# magicmouth-v0_1.net
KiCad netlist of a schematic drawn in EAGLE
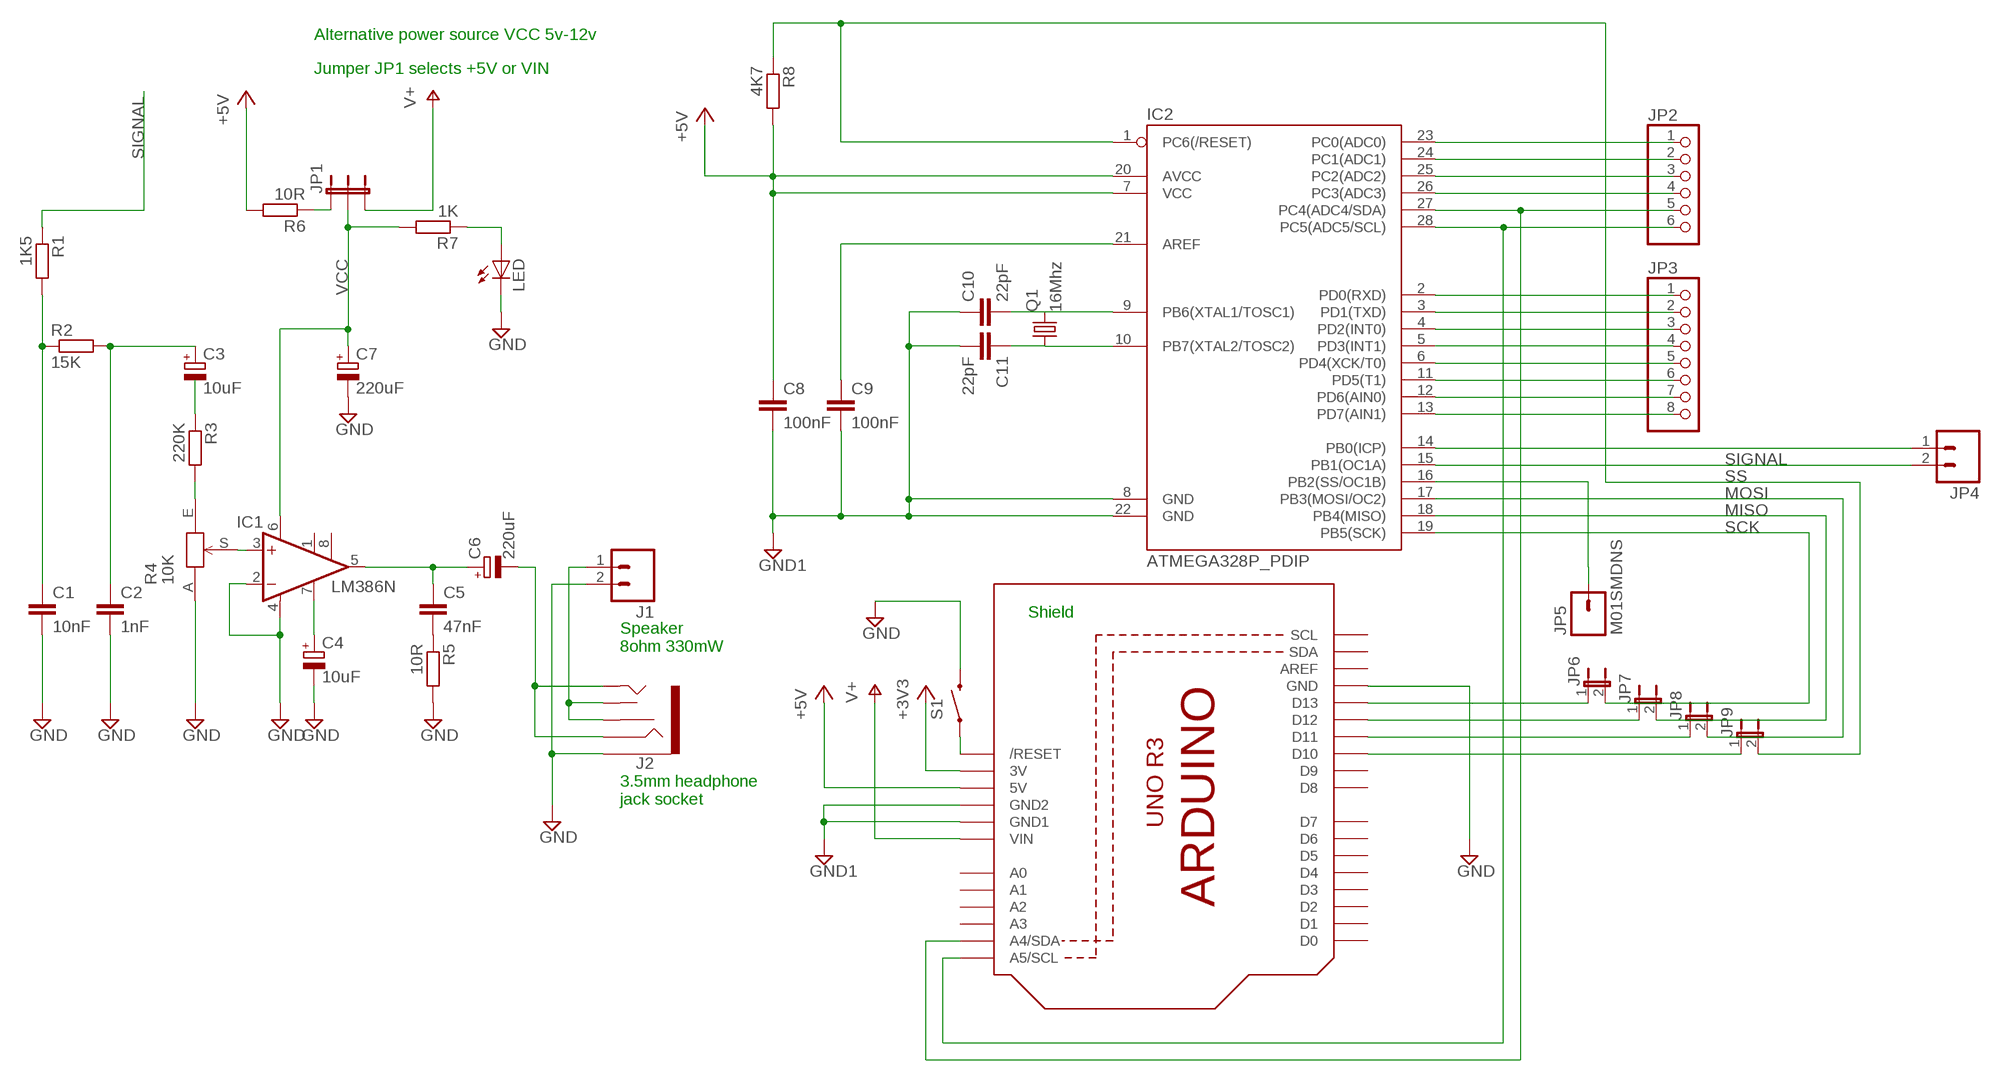
[diagram p0: schematic, sheet 1]

(export (version "E")
  (design (tool "Eeschema 10.0.6"))
  (components
    (comp (ref "C1")
      (value "10nF")
      (footprint "eagle-import:C050-025X075")
      (libsource (lib "eagle-import") (part "resistor_C-EU050-025X075"))
    )
    (comp (ref "C2")
      (value "1nF")
      (footprint "eagle-import:C050-025X075")
      (libsource (lib "eagle-import") (part "resistor_C-EU050-025X075"))
    )
    (comp (ref "C3")
      (value "10uF")
      (footprint "eagle-import:E2,5-7")
      (libsource (lib "eagle-import") (part "CPOL-EUE2.5-7"))
    )
    (comp (ref "C4")
      (value "10uF")
      (footprint "eagle-import:E2,5-7")
      (libsource (lib "eagle-import") (part "CPOL-EUE2.5-7"))
    )
    (comp (ref "C5")
      (value "47nF")
      (footprint "eagle-import:C050-025X075")
      (libsource (lib "eagle-import") (part "resistor_C-EU050-025X075"))
    )
    (comp (ref "C6")
      (value "220uF")
      (footprint "eagle-import:TT5D7L")
      (libsource (lib "eagle-import") (part "CPOL-EUTT5D7L"))
    )
    (comp (ref "C7")
      (value "220uF")
      (footprint "eagle-import:TT5D7L")
      (libsource (lib "eagle-import") (part "CPOL-EUTT5D7L"))
    )
    (comp (ref "C8")
      (value "100nF")
      (footprint "eagle-import:C025-025X050")
      (fields (field (name "CAPACITANCE") "10 nF"))
      (libsource (lib "eagle-import") (part "C-EU025-025X050"))
    )
    (comp (ref "C9")
      (value "100nF")
      (footprint "eagle-import:C025-025X050")
      (fields (field (name "CAPACITANCE") "100 nF"))
      (libsource (lib "eagle-import") (part "C-EU025-025X050"))
    )
    (comp (ref "C10")
      (value "22pF")
      (footprint "eagle-import:C025-025X050")
      (fields (field (name "CAPACITANCE") "22 pf"))
      (libsource (lib "eagle-import") (part "C-EU025-025X050"))
    )
    (comp (ref "C11")
      (value "22pF")
      (footprint "eagle-import:C025-025X050")
      (fields (field (name "CAPACITANCE") "22 pf"))
      (libsource (lib "eagle-import") (part "C-EU025-025X050"))
    )
    (comp (ref "IC1")
      (value "LM386N")
      (footprint "eagle-import:DIL08")
      (libsource (lib "eagle-import") (part "LM386?-N1"))
    )
    (comp (ref "IC2")
      (value "ATMEGA328P_PDIP")
      (footprint "eagle-import:DIL28-3")
      (libsource (lib "eagle-import") (part "ATMEGA328P_PDIP"))
    )
    (comp (ref "J1")
      (value "M023.5MM")
      (footprint "eagle-import:SCREWTERMINAL-3.5MM-2")
      (libsource (lib "eagle-import") (part "M023.5MM"))
    )
    (comp (ref "J2")
      (value "AUDIO-JACK2PTH")
      (footprint "eagle-import:AUDIO-JACK")
      (libsource (lib "eagle-import") (part "AUDIO-JACK2PTH"))
    )
    (comp (ref "JP1")
      (value "JUMPER-3PTH")
      (footprint "eagle-import:1X03")
      (libsource (lib "eagle-import") (part "JUMPER-3PTH"))
    )
    (comp (ref "JP2")
      (value "PINHD-1X6CB")
      (footprint "eagle-import:1X06-CLEANBIG")
      (libsource (lib "eagle-import") (part "PINHD-1X6CB"))
    )
    (comp (ref "JP3")
      (value "PINHD-1X8CLEANBIG")
      (footprint "eagle-import:1X08-CLEANBIG")
      (libsource (lib "eagle-import") (part "PINHD-1X8CLEANBIG"))
    )
    (comp (ref "JP4")
      (value "M021X02_NO_SILK")
      (footprint "eagle-import:1X02_NO_SILK")
      (libsource (lib "eagle-import") (part "M021X02_NO_SILK"))
    )
    (comp (ref "JP5")
      (value "M01SMDNS")
      (footprint "eagle-import:1X01NS")
      (libsource (lib "eagle-import") (part "M01SMDNS"))
    )
    (comp (ref "JP6")
      (value "JUMPER-2PTH")
      (footprint "eagle-import:1X02")
      (libsource (lib "eagle-import") (part "JUMPER-2PTH"))
    )
    (comp (ref "JP7")
      (value "JUMPER-2PTH")
      (footprint "eagle-import:1X02")
      (libsource (lib "eagle-import") (part "JUMPER-2PTH"))
    )
    (comp (ref "JP8")
      (value "JUMPER-2PTH")
      (footprint "eagle-import:1X02")
      (libsource (lib "eagle-import") (part "JUMPER-2PTH"))
    )
    (comp (ref "JP9")
      (value "JUMPER-2PTH")
      (footprint "eagle-import:1X02")
      (libsource (lib "eagle-import") (part "JUMPER-2PTH"))
    )
    (comp (ref "LED")
      (value "LED3MM")
      (footprint "eagle-import:LED3MM")
      (libsource (lib "eagle-import") (part "LED3MM"))
    )
    (comp (ref "Q1")
      (value "16Mhz")
      (footprint "eagle-import:HC49_S")
      (libsource (lib "eagle-import") (part "CRYSTALHC49S"))
    )
    (comp (ref "R1")
      (value "1K5")
      (footprint "eagle-import:0207_7")
      (libsource (lib "eagle-import") (part "R-EU_0207/7"))
    )
    (comp (ref "R2")
      (value "15K")
      (footprint "eagle-import:0207_7")
      (libsource (lib "eagle-import") (part "R-EU_0207/7"))
    )
    (comp (ref "R3")
      (value "220K")
      (footprint "eagle-import:0207_7")
      (libsource (lib "eagle-import") (part "R-EU_0207/7"))
    )
    (comp (ref "R4")
      (value "10K")
      (footprint "eagle-import:3352T")
      (libsource (lib "eagle-import") (part "TPOT3352"))
    )
    (comp (ref "R5")
      (value "10R")
      (footprint "eagle-import:0207_7")
      (libsource (lib "eagle-import") (part "resistor_R-EU_0207/7"))
    )
    (comp (ref "R6")
      (value "10R")
      (footprint "eagle-import:0207_7")
      (libsource (lib "eagle-import") (part "R-EU_0207/7"))
    )
    (comp (ref "R7")
      (value "1K")
      (footprint "eagle-import:0207_7")
      (libsource (lib "eagle-import") (part "R-EU_0207/7"))
    )
    (comp (ref "R8")
      (value "4K7")
      (footprint "eagle-import:0207_7")
      (fields (field (name "RESISTANCE") "4K7"))
      (libsource (lib "eagle-import") (part "R-EU_0207/7"))
    )
    (comp (ref "S1")
      (value "SWITCH-MOMENTARY-2PTH")
      (footprint "eagle-import:TACTILE-PTH")
      (libsource (lib "eagle-import") (part "SWITCH-MOMENTARY-2PTH"))
    )
    (comp (ref "U1")
      (value "ARDUINOR3-NOIOREF-NOTEXT")
      (footprint "eagle-import:ARDUINOR3-NOTEXT-NOIOREF")
      (libsource (lib "eagle-import") (part "ARDUINOR3-NOIOREF-NOTEXT"))
    )
  )
  (nets
    (net (code "1") (name "+3V3") (class "Default")
      (node (ref "U1") (pin "3V") (pinfunction "3V_3V") (pintype "power_in"))
    )
    (net (code "2") (name "+5V") (class "Default")
      (node (ref "C8") (pin "1") (pinfunction "1_1") (pintype "passive"))
      (node (ref "IC2") (pin "20") (pinfunction "AVCC_20") (pintype "bidirectional"))
      (node (ref "IC2") (pin "7") (pinfunction "VCC_7") (pintype "bidirectional"))
      (node (ref "R6") (pin "2") (pinfunction "2_2") (pintype "passive"))
      (node (ref "R8") (pin "2") (pinfunction "2_2") (pintype "passive"))
      (node (ref "U1") (pin "5V") (pinfunction "5V_5V") (pintype "power_in"))
    )
    (net (code "3") (name "/MISO") (class "Default")
      (node (ref "IC2") (pin "18") (pinfunction "PB4(MISO)_18") (pintype "bidirectional"))
      (node (ref "JP7") (pin "2") (pinfunction "2_2") (pintype "passive"))
    )
    (net (code "4") (name "/MOSI") (class "Default")
      (node (ref "IC2") (pin "17") (pinfunction "PB3(MOSI/OC2)_17") (pintype "bidirectional"))
      (node (ref "JP8") (pin "2") (pinfunction "2_2") (pintype "passive"))
    )
    (net (code "5") (name "/SCK") (class "Default")
      (node (ref "IC2") (pin "19") (pinfunction "PB5(SCK)_19") (pintype "bidirectional"))
      (node (ref "JP6") (pin "2") (pinfunction "2_2") (pintype "passive"))
    )
    (net (code "6") (name "/SIGNAL") (class "Default")
      (node (ref "IC2") (pin "15") (pinfunction "PB1(OC1A)_15") (pintype "bidirectional"))
      (node (ref "JP4") (pin "2") (pinfunction "2_2") (pintype "passive"))
      (node (ref "R1") (pin "1") (pinfunction "1_1") (pintype "passive"))
    )
    (net (code "7") (name "/SS") (class "Default")
      (node (ref "IC2") (pin "1") (pinfunction "PC6(/RESET)_1") (pintype "bidirectional"))
      (node (ref "JP9") (pin "2") (pinfunction "2_2") (pintype "passive"))
      (node (ref "R8") (pin "1") (pinfunction "1_1") (pintype "passive"))
    )
    (net (code "8") (name "/VCC") (class "Default")
      (node (ref "C7") (pin "+") (pinfunction "+_+") (pintype "passive"))
      (node (ref "IC1") (pin "6") (pinfunction "VS_6") (pintype "power_in"))
      (node (ref "JP1") (pin "2") (pinfunction "2_2") (pintype "passive"))
      (node (ref "R7") (pin "2") (pinfunction "2_2") (pintype "passive"))
    )
    (net (code "9") (name "GND") (class "Default")
      (node (ref "C1") (pin "2") (pinfunction "2_2") (pintype "passive"))
      (node (ref "C2") (pin "2") (pinfunction "2_2") (pintype "passive"))
      (node (ref "C4") (pin "-") (pinfunction "-_-") (pintype "passive"))
      (node (ref "C7") (pin "-") (pinfunction "-_-") (pintype "passive"))
      (node (ref "IC1") (pin "2") (pinfunction "-IN_2") (pintype "input"))
      (node (ref "IC1") (pin "4") (pinfunction "GND_4") (pintype "power_in"))
      (node (ref "J1") (pin "2") (pinfunction "2_2") (pintype "passive"))
      (node (ref "J2") (pin "SLEEVE") (pinfunction "SLEEVE_SLEEVE") (pintype "bidirectional"))
      (node (ref "LED") (pin "K") (pinfunction "C_K") (pintype "passive"))
      (node (ref "R4") (pin "A") (pinfunction "A_A") (pintype "passive"))
      (node (ref "R5") (pin "2") (pinfunction "2_2") (pintype "passive"))
      (node (ref "S1") (pin "3") (pinfunction "2_3") (pintype "passive"))
      (node (ref "U1") (pin "GND") (pinfunction "GND_GND") (pintype "power_in"))
    )
    (net (code "10") (name "GND1") (class "Default")
      (node (ref "C10") (pin "1") (pinfunction "1_1") (pintype "passive"))
      (node (ref "C11") (pin "2") (pinfunction "2_2") (pintype "passive"))
      (node (ref "C8") (pin "2") (pinfunction "2_2") (pintype "passive"))
      (node (ref "C9") (pin "2") (pinfunction "2_2") (pintype "passive"))
      (node (ref "IC2") (pin "22") (pinfunction "GND_22") (pintype "bidirectional"))
      (node (ref "IC2") (pin "8") (pinfunction "GND_8") (pintype "bidirectional"))
      (node (ref "U1") (pin "GND1") (pinfunction "GND1_GND1") (pintype "power_in"))
      (node (ref "U1") (pin "GND2") (pinfunction "GND2_GND2") (pintype "power_in"))
    )
    (net (code "11") (name "Net-(C1-Pad1)") (class "Default")
      (node (ref "C1") (pin "1") (pinfunction "1_1") (pintype "passive"))
      (node (ref "R1") (pin "2") (pinfunction "2_2") (pintype "passive"))
      (node (ref "R2") (pin "1") (pinfunction "1_1") (pintype "passive"))
    )
    (net (code "12") (name "Net-(C2-Pad1)") (class "Default")
      (node (ref "C2") (pin "1") (pinfunction "1_1") (pintype "passive"))
      (node (ref "C3") (pin "+") (pinfunction "+_+") (pintype "passive"))
      (node (ref "R2") (pin "2") (pinfunction "2_2") (pintype "passive"))
    )
    (net (code "13") (name "Net-(C3-Pad-)") (class "Default")
      (node (ref "C3") (pin "-") (pinfunction "-_-") (pintype "passive"))
      (node (ref "R3") (pin "1") (pinfunction "1_1") (pintype "passive"))
    )
    (net (code "14") (name "Net-(C5-Pad2)") (class "Default")
      (node (ref "C5") (pin "2") (pinfunction "2_2") (pintype "passive"))
      (node (ref "R5") (pin "1") (pinfunction "1_1") (pintype "passive"))
    )
    (net (code "15") (name "Net-(C6-Pad-)") (class "Default")
      (node (ref "C6") (pin "-") (pinfunction "-_-") (pintype "passive"))
      (node (ref "J2") (pin "RING") (pinfunction "RING_RING") (pintype "bidirectional"))
      (node (ref "J2") (pin "TIP") (pinfunction "TIP_TIP") (pintype "bidirectional"))
    )
    (net (code "16") (name "Net-(IC1-+IN)") (class "Default")
      (node (ref "IC1") (pin "3") (pinfunction "+IN_3") (pintype "input"))
      (node (ref "R4") (pin "S") (pinfunction "S_S") (pintype "passive"))
    )
    (net (code "17") (name "Net-(IC1-BYPASS)") (class "Default")
      (node (ref "C4") (pin "+") (pinfunction "+_+") (pintype "passive"))
      (node (ref "IC1") (pin "7") (pinfunction "BYPASS_7") (pintype "passive"))
    )
    (net (code "18") (name "Net-(IC1-OUT)") (class "Default")
      (node (ref "C5") (pin "1") (pinfunction "1_1") (pintype "passive"))
      (node (ref "C6") (pin "+") (pinfunction "+_+") (pintype "passive"))
      (node (ref "IC1") (pin "5") (pinfunction "OUT_5") (pintype "output"))
    )
    (net (code "19") (name "Net-(IC2-AREF)") (class "Default")
      (node (ref "C9") (pin "1") (pinfunction "1_1") (pintype "passive"))
      (node (ref "IC2") (pin "21") (pinfunction "AREF_21") (pintype "bidirectional"))
    )
    (net (code "20") (name "Net-(IC2-PB0(ICP))") (class "Default")
      (node (ref "IC2") (pin "14") (pinfunction "PB0(ICP)_14") (pintype "bidirectional"))
      (node (ref "JP4") (pin "1") (pinfunction "1_1") (pintype "passive"))
    )
    (net (code "21") (name "Net-(IC2-PB2(SS{slash}OC1B))") (class "Default")
      (node (ref "IC2") (pin "16") (pinfunction "PB2(SS/OC1B)_16") (pintype "bidirectional"))
      (node (ref "JP5") (pin "1") (pinfunction "1_1") (pintype "passive"))
    )
    (net (code "22") (name "Net-(IC2-PB6(XTAL1{slash}TOSC1))") (class "Default")
      (node (ref "C10") (pin "2") (pinfunction "2_2") (pintype "passive"))
      (node (ref "IC2") (pin "9") (pinfunction "PB6(XTAL1/TOSC1)_9") (pintype "bidirectional"))
      (node (ref "Q1") (pin "2") (pinfunction "2_2") (pintype "passive"))
    )
    (net (code "23") (name "Net-(IC2-PB7(XTAL2{slash}TOSC2))") (class "Default")
      (node (ref "C11") (pin "1") (pinfunction "1_1") (pintype "passive"))
      (node (ref "IC2") (pin "10") (pinfunction "PB7(XTAL2/TOSC2)_10") (pintype "bidirectional"))
      (node (ref "Q1") (pin "1") (pinfunction "1_1") (pintype "passive"))
    )
    (net (code "24") (name "Net-(IC2-PC0(ADC0))") (class "Default")
      (node (ref "IC2") (pin "23") (pinfunction "PC0(ADC0)_23") (pintype "bidirectional"))
      (node (ref "JP2") (pin "1") (pinfunction "1_1") (pintype "passive"))
    )
    (net (code "25") (name "Net-(IC2-PC1(ADC1))") (class "Default")
      (node (ref "IC2") (pin "24") (pinfunction "PC1(ADC1)_24") (pintype "bidirectional"))
      (node (ref "JP2") (pin "2") (pinfunction "2_2") (pintype "passive"))
    )
    (net (code "26") (name "Net-(IC2-PC2(ADC2))") (class "Default")
      (node (ref "IC2") (pin "25") (pinfunction "PC2(ADC2)_25") (pintype "bidirectional"))
      (node (ref "JP2") (pin "3") (pinfunction "3_3") (pintype "passive"))
    )
    (net (code "27") (name "Net-(IC2-PC3(ADC3))") (class "Default")
      (node (ref "IC2") (pin "26") (pinfunction "PC3(ADC3)_26") (pintype "bidirectional"))
      (node (ref "JP2") (pin "4") (pinfunction "4_4") (pintype "passive"))
    )
    (net (code "28") (name "Net-(IC2-PC4(ADC4{slash}SDA))") (class "Default")
      (node (ref "IC2") (pin "27") (pinfunction "PC4(ADC4/SDA)_27") (pintype "bidirectional"))
      (node (ref "JP2") (pin "5") (pinfunction "5_5") (pintype "passive"))
      (node (ref "U1") (pin "A4") (pinfunction "A4/SDA_A4") (pintype "bidirectional"))
    )
    (net (code "29") (name "Net-(IC2-PC5(ADC5{slash}SCL))") (class "Default")
      (node (ref "IC2") (pin "28") (pinfunction "PC5(ADC5/SCL)_28") (pintype "bidirectional"))
      (node (ref "JP2") (pin "6") (pinfunction "6_6") (pintype "passive"))
      (node (ref "U1") (pin "A5") (pinfunction "A5/SCL_A5") (pintype "bidirectional"))
    )
    (net (code "30") (name "Net-(IC2-PD0(RXD))") (class "Default")
      (node (ref "IC2") (pin "2") (pinfunction "PD0(RXD)_2") (pintype "bidirectional"))
      (node (ref "JP3") (pin "1") (pinfunction "1_1") (pintype "passive"))
    )
    (net (code "31") (name "Net-(IC2-PD1(TXD))") (class "Default")
      (node (ref "IC2") (pin "3") (pinfunction "PD1(TXD)_3") (pintype "bidirectional"))
      (node (ref "JP3") (pin "2") (pinfunction "2_2") (pintype "passive"))
    )
    (net (code "32") (name "Net-(IC2-PD2(INT0))") (class "Default")
      (node (ref "IC2") (pin "4") (pinfunction "PD2(INT0)_4") (pintype "bidirectional"))
      (node (ref "JP3") (pin "3") (pinfunction "3_3") (pintype "passive"))
    )
    (net (code "33") (name "Net-(IC2-PD3(INT1))") (class "Default")
      (node (ref "IC2") (pin "5") (pinfunction "PD3(INT1)_5") (pintype "bidirectional"))
      (node (ref "JP3") (pin "4") (pinfunction "4_4") (pintype "passive"))
    )
    (net (code "34") (name "Net-(IC2-PD4(XCK{slash}T0))") (class "Default")
      (node (ref "IC2") (pin "6") (pinfunction "PD4(XCK/T0)_6") (pintype "bidirectional"))
      (node (ref "JP3") (pin "5") (pinfunction "5_5") (pintype "passive"))
    )
    (net (code "35") (name "Net-(IC2-PD5(T1))") (class "Default")
      (node (ref "IC2") (pin "11") (pinfunction "PD5(T1)_11") (pintype "bidirectional"))
      (node (ref "JP3") (pin "6") (pinfunction "6_6") (pintype "passive"))
    )
    (net (code "36") (name "Net-(IC2-PD6(AIN0))") (class "Default")
      (node (ref "IC2") (pin "12") (pinfunction "PD6(AIN0)_12") (pintype "bidirectional"))
      (node (ref "JP3") (pin "7") (pinfunction "7_7") (pintype "passive"))
    )
    (net (code "37") (name "Net-(IC2-PD7(AIN1))") (class "Default")
      (node (ref "IC2") (pin "13") (pinfunction "PD7(AIN1)_13") (pintype "bidirectional"))
      (node (ref "JP3") (pin "8") (pinfunction "8_8") (pintype "passive"))
    )
    (net (code "38") (name "Net-(J1-Pad1)") (class "Default")
      (node (ref "J1") (pin "1") (pinfunction "1_1") (pintype "passive"))
      (node (ref "J2") (pin "RSH") (pinfunction "RSH_RSH") (pintype "bidirectional"))
      (node (ref "J2") (pin "TSH") (pinfunction "TSH_TSH") (pintype "bidirectional"))
    )
    (net (code "39") (name "Net-(JP1-Pad1)") (class "Default")
      (node (ref "JP1") (pin "1") (pinfunction "1_1") (pintype "passive"))
      (node (ref "R6") (pin "1") (pinfunction "1_1") (pintype "passive"))
    )
    (net (code "40") (name "Net-(JP6-Pad1)") (class "Default")
      (node (ref "JP6") (pin "1") (pinfunction "1_1") (pintype "passive"))
      (node (ref "U1") (pin "D13") (pinfunction "D13_D13") (pintype "bidirectional"))
    )
    (net (code "41") (name "Net-(JP7-Pad1)") (class "Default")
      (node (ref "JP7") (pin "1") (pinfunction "1_1") (pintype "passive"))
      (node (ref "U1") (pin "D12") (pinfunction "D12_D12") (pintype "bidirectional"))
    )
    (net (code "42") (name "Net-(JP8-Pad1)") (class "Default")
      (node (ref "JP8") (pin "1") (pinfunction "1_1") (pintype "passive"))
      (node (ref "U1") (pin "D11") (pinfunction "D11_D11") (pintype "bidirectional"))
    )
    (net (code "43") (name "Net-(JP9-Pad1)") (class "Default")
      (node (ref "JP9") (pin "1") (pinfunction "1_1") (pintype "passive"))
      (node (ref "U1") (pin "D10") (pinfunction "D10_D10") (pintype "bidirectional"))
    )
    (net (code "44") (name "Net-(LED-PadA)") (class "Default")
      (node (ref "LED") (pin "A") (pinfunction "A_A") (pintype "passive"))
      (node (ref "R7") (pin "1") (pinfunction "1_1") (pintype "passive"))
    )
    (net (code "45") (name "Net-(R3-Pad2)") (class "Default")
      (node (ref "R3") (pin "2") (pinfunction "2_2") (pintype "passive"))
      (node (ref "R4") (pin "E") (pinfunction "E_E") (pintype "passive"))
    )
    (net (code "46") (name "Net-(U1-{slash}RESET)") (class "Default")
      (node (ref "S1") (pin "1") (pinfunction "1_1") (pintype "passive"))
      (node (ref "U1") (pin "RESET") (pinfunction "/RESET_RESET") (pintype "bidirectional"))
    )
    (net (code "47") (name "V+") (class "Default")
      (node (ref "JP1") (pin "3") (pinfunction "3_3") (pintype "passive"))
      (node (ref "U1") (pin "VIN") (pinfunction "VIN_VIN") (pintype "power_in"))
    )
    (net (code "48") (name "unconnected-(IC1-GAIN-Pad1)") (class "Default")
      (node (ref "IC1") (pin "1") (pinfunction "GAIN_1") (pintype "passive"))
    )
    (net (code "49") (name "unconnected-(IC1-GAIN-Pad8)") (class "Default")
      (node (ref "IC1") (pin "8") (pinfunction "GAIN_8") (pintype "passive"))
    )
    (net (code "50") (name "unconnected-(U1-PadA0)") (class "Default")
      (node (ref "U1") (pin "A0") (pinfunction "A0_A0") (pintype "bidirectional"))
    )
    (net (code "51") (name "unconnected-(U1-PadA1)") (class "Default")
      (node (ref "U1") (pin "A1") (pinfunction "A1_A1") (pintype "bidirectional"))
    )
    (net (code "52") (name "unconnected-(U1-PadA2)") (class "Default")
      (node (ref "U1") (pin "A2") (pinfunction "A2_A2") (pintype "bidirectional"))
    )
    (net (code "53") (name "unconnected-(U1-PadA3)") (class "Default")
      (node (ref "U1") (pin "A3") (pinfunction "A3_A3") (pintype "bidirectional"))
    )
    (net (code "54") (name "unconnected-(U1-PadAREF)") (class "Default")
      (node (ref "U1") (pin "AREF") (pinfunction "AREF_AREF") (pintype "bidirectional"))
    )
    (net (code "55") (name "unconnected-(U1-PadD0)") (class "Default")
      (node (ref "U1") (pin "D0") (pinfunction "D0_D0") (pintype "bidirectional"))
    )
    (net (code "56") (name "unconnected-(U1-PadD1)") (class "Default")
      (node (ref "U1") (pin "D1") (pinfunction "D1_D1") (pintype "bidirectional"))
    )
    (net (code "57") (name "unconnected-(U1-PadD2)") (class "Default")
      (node (ref "U1") (pin "D2") (pinfunction "D2_D2") (pintype "bidirectional"))
    )
    (net (code "58") (name "unconnected-(U1-PadD3)") (class "Default")
      (node (ref "U1") (pin "D3") (pinfunction "D3_D3") (pintype "bidirectional"))
    )
    (net (code "59") (name "unconnected-(U1-PadD4)") (class "Default")
      (node (ref "U1") (pin "D4") (pinfunction "D4_D4") (pintype "bidirectional"))
    )
    (net (code "60") (name "unconnected-(U1-PadD5)") (class "Default")
      (node (ref "U1") (pin "D5") (pinfunction "D5_D5") (pintype "bidirectional"))
    )
    (net (code "61") (name "unconnected-(U1-PadD6)") (class "Default")
      (node (ref "U1") (pin "D6") (pinfunction "D6_D6") (pintype "bidirectional"))
    )
    (net (code "62") (name "unconnected-(U1-PadD7)") (class "Default")
      (node (ref "U1") (pin "D7") (pinfunction "D7_D7") (pintype "bidirectional"))
    )
    (net (code "63") (name "unconnected-(U1-PadD8)") (class "Default")
      (node (ref "U1") (pin "D8") (pinfunction "D8_D8") (pintype "bidirectional"))
    )
    (net (code "64") (name "unconnected-(U1-PadD9)") (class "Default")
      (node (ref "U1") (pin "D9") (pinfunction "D9_D9") (pintype "bidirectional"))
    )
    (net (code "65") (name "unconnected-(U1-PadSCL)") (class "Default")
      (node (ref "U1") (pin "SCL") (pinfunction "SCL_SCL") (pintype "bidirectional"))
    )
    (net (code "66") (name "unconnected-(U1-PadSDA)") (class "Default")
      (node (ref "U1") (pin "SDA") (pinfunction "SDA_SDA") (pintype "bidirectional"))
    )
  )
)
